# IO.net
KiCad netlist of a schematic drawn in Altium Designer
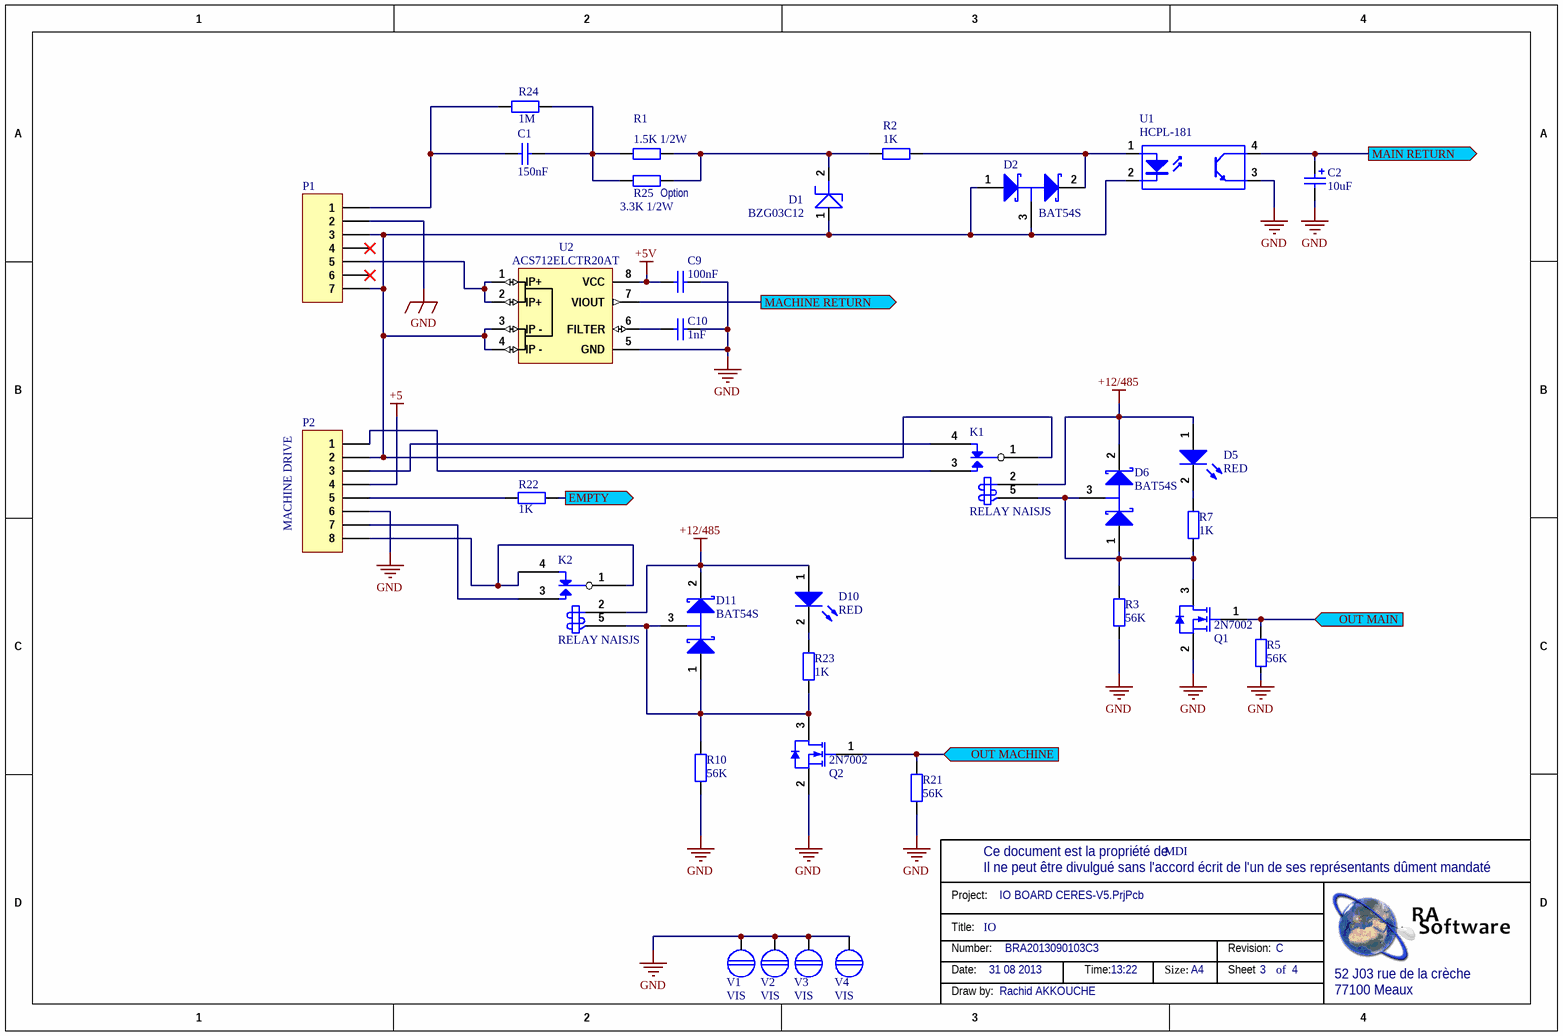
[diagram p0: IO.SchDoc]

(export (version "E")
  (design (tool "Eeschema 10.0.6"))
  (components
    (comp (ref "C1")
      (value "150nF")
      (footprint "C1210")
      (description "Capacitor")
      (fields
        (field (name "MANUFACTURER") "KEMET")
        (field (name "MANUFACTURER PART NUMBER") "C1210V154KCRACTU")
      )
      (libsource (lib "Miscellaneous Devices") (part "Cap"))
    )
    (comp (ref "C2")
      (value "10uF")
      (footprint "SYLANN:C0805")
      (description "Polarized Capacitor")
      (fields
        (field (name "MANUFACTURER") "EPCOS")
        (field (name "MANUFACTURER PART NUMBER") "B41142A4107M")
        (field (name "HAUTEUR") "7.7")
        (field (name "LONGUEUR/HAUTEUR") "7.7")
      )
      (libsource (lib "BRA") (part "Cap Pol 100uF"))
    )
    (comp (ref "C9")
      (value "100nF")
      (footprint "SYLANN:C0805")
      (description "Capacitor")
      (fields
        (field (name "MANUFACTURER") "MULTICOMP")
        (field (name "MANUFACTURER PART NUMBER") "MCCA000296")
      )
      (libsource (lib "BRA") (part "Cap 0805 100nF"))
    )
    (comp (ref "C10")
      (value "1nF")
      (footprint "SYLANN:C0805")
      (description "Capacitor")
      (fields
        (field (name "MANUFACTURER") "SAMSUNG")
        (field (name "MANUFACTURER PART NUMBER") "CL05B102KB5NNNC")
      )
      (libsource (lib "BRA") (part "Cap 0805 1nF"))
    )
    (comp (ref "D1")
      (value "BZG03C12")
      (footprint "sma")
      (fields (field (name "MANUFACTURER") "VISHAY") (field (name "MANUFACTURER PART NUMBER") "BZG03C12TR3"))
      (libsource (lib "UTIL_Library") (part "DZ"))
    )
    (comp (ref "D2")
      (value "BAT54S")
      (footprint "SOT23")
      (description "Schottky Barrier Double Diode")
      (fields (field (name "MANUFACTURER") "MULTICOMP"))
      (libsource (lib "Ares") (part "BAT54S"))
    )
    (comp (ref "D5")
      (value "HSMH-C190")
      (footprint "0603-LEDR")
      (description "Surface Mount Chip LED, Red")
      (fields
        (field (name "MANUFACTURER") "AVAGO TECHNOLOGIES")
        (field (name "MANUFACTURER PART NUMBER") "HSMH-C190.")
        (field (name "COULEUR") "RED")
        (field (name "LONGUEUR/HAUTEUR") "1.6")
      )
      (libsource (lib "BRA") (part "HSMH-C190"))
    )
    (comp (ref "D6")
      (value "BAT54S")
      (footprint "SOT23")
      (description "Schottky Barrier Double Diode")
      (fields (field (name "MANUFACTURER") "MULTICOMP"))
      (libsource (lib "Ares") (part "BAT54S"))
    )
    (comp (ref "D10")
      (value "HSMH-C190")
      (footprint "0603-LEDR")
      (description "Surface Mount Chip LED, Red")
      (fields
        (field (name "MANUFACTURER") "AVAGO TECHNOLOGIES")
        (field (name "MANUFACTURER PART NUMBER") "HSMH-C190.")
        (field (name "COULEUR") "RED")
        (field (name "LONGUEUR/HAUTEUR") "1.6")
      )
      (libsource (lib "BRA") (part "HSMH-C190"))
    )
    (comp (ref "D11")
      (value "BAT54S")
      (footprint "SOT23")
      (description "Schottky Barrier Double Diode")
      (fields (field (name "MANUFACTURER") "MULTICOMP"))
      (libsource (lib "Ares") (part "BAT54S"))
    )
    (comp (ref "K1")
      (value "RELAY NAISJS")
      (footprint "RELAIG5L")
      (fields
        (field (name "MANUFACTURER") "OMRON ELECTRONIC COMPONENTS")
        (field (name "MANUFACTURER PART NUMBER") "G5LA1A412DC")
        (field (name "HAUTEUR, DIMENSION EXTERNE") "15.8")
      )
      (libsource (lib "UTIL_Library") (part "RELAY NAISJS"))
    )
    (comp (ref "K2")
      (value "RELAY NAISJS")
      (footprint "RELAIG5L")
      (fields
        (field (name "MANUFACTURER") "OMRON ELECTRONIC COMPONENTS")
        (field (name "MANUFACTURER PART NUMBER") "G5LA1A412DC")
        (field (name "HAUTEUR, DIMENSION EXTERNE") "15.8")
      )
      (libsource (lib "UTIL_Library") (part "RELAY NAISJS"))
    )
    (comp (ref "P1")
      (value "Header 7")
      (footprint "CO7P508-90")
      (description "Header, 7-Pin")
      (fields
        (field (name "MANUFACTURER") "FCI")
        (field (name "MANUFACTURER PART NUMBER") "20020110-H071A01LF")
        (field (name "PUBLISHER") "Altium Limited")
      )
      (libsource (lib "Miscellaneous Connectors") (part "Header 7"))
    )
    (comp (ref "P2")
      (value "Header 8")
      (footprint "CO8P508 - 90°")
      (description "Header, 8-Pin")
      (fields
        (field (name "MANUFACTURER") "CAMDENBOSS")
        (field (name "MANUFACTURER PART NUMBER") "CTB9350/8AO")
        (field (name "PUBLISHER") "Altium Limited")
      )
      (libsource (lib "Miscellaneous Connectors") (part "Header 8"))
    )
    (comp (ref "Q1")
      (value "2N7002")
      (footprint "SOT23")
      (description "N-channel Enhancement Mode Field-effect Transistor")
      (fields (field (name "MANUFACTURER") "FAIRCHILD SEMICONDUCTOR"))
      (libsource (lib "BRA") (part "2N7002"))
    )
    (comp (ref "Q2")
      (value "2N7002")
      (footprint "SOT23")
      (description "N-channel Enhancement Mode Field-effect Transistor")
      (fields (field (name "MANUFACTURER") "FAIRCHILD SEMICONDUCTOR"))
      (libsource (lib "BRA") (part "2N7002"))
    )
    (comp (ref "R1")
      (value "1.5K 1/2W")
      (footprint "1206 - 2010")
      (description "Resistor")
      (fields (field (name "MANUFACTURER") "WALSIN") (field (name "MANUFACTURER PART NUMBER") "WF12P3301FTL"))
      (libsource (lib "BRA") (part "Resistor 0805 470"))
    )
    (comp (ref "R2")
      (value "1K")
      (footprint "R0805")
      (description "Resistor")
      (fields
        (field (name "MANUFACTURER") "MULTICOMP")
        (field (name "MANUFACTURER PART NUMBER") "MC0.1W08051%1KFR")
      )
      (libsource (lib "Miscellaneous Devices") (part "Res2"))
    )
    (comp (ref "R3")
      (value "56K")
      (footprint "R0805")
      (description "Resistor")
      (fields
        (field (name "MANUFACTURER") "MULTICOMP")
        (field (name "MANUFACTURER PART NUMBER") "MC0.1W08051%56KFR")
      )
      (libsource (lib "BRA") (part "Resistor 0805 56K"))
    )
    (comp (ref "R5")
      (value "56K")
      (footprint "R0805")
      (description "Resistor")
      (fields
        (field (name "MANUFACTURER") "MULTICOMP")
        (field (name "MANUFACTURER PART NUMBER") "MC0.1W08051%56KFR")
      )
      (libsource (lib "BRA") (part "Resistor 0805 56K"))
    )
    (comp (ref "R7")
      (value "1K")
      (footprint "R0805")
      (description "Resistor")
      (fields
        (field (name "MANUFACTURER") "MULTICOMP")
        (field (name "MANUFACTURER PART NUMBER") "MC0.1W08051%1KFR")
      )
      (libsource (lib "BRA") (part "Resistor 0805 1K"))
    )
    (comp (ref "R10")
      (value "56K")
      (footprint "R0805")
      (description "Resistor")
      (fields
        (field (name "MANUFACTURER") "MULTICOMP")
        (field (name "MANUFACTURER PART NUMBER") "MC0.1W08051%56KFR")
      )
      (libsource (lib "BRA") (part "Resistor 0805 56K"))
    )
    (comp (ref "R21")
      (value "56K")
      (footprint "R0805")
      (description "Resistor")
      (fields
        (field (name "MANUFACTURER") "MULTICOMP")
        (field (name "MANUFACTURER PART NUMBER") "MC0.1W08051%56KFR")
      )
      (libsource (lib "BRA") (part "Resistor 0805 56K"))
    )
    (comp (ref "R22")
      (value "1K")
      (footprint "R0805")
      (description "Resistor")
      (fields
        (field (name "MANUFACTURER") "MULTICOMP")
        (field (name "MANUFACTURER PART NUMBER") "MC0.1W08051%1KFR")
      )
      (libsource (lib "") (part "Resistor 0805 1K_1"))
    )
    (comp (ref "R23")
      (value "1K")
      (footprint "R0805")
      (description "Resistor")
      (fields
        (field (name "MANUFACTURER") "MULTICOMP")
        (field (name "MANUFACTURER PART NUMBER") "MC0.1W08051%1KFR")
      )
      (libsource (lib "BRA") (part "Resistor 0805 1K"))
    )
    (comp (ref "R24")
      (value "1M")
      (footprint "R1206")
      (description "Resistor")
      (fields
        (field (name "MANUFACTURER") "PANASONIC ELECTRONIC COMPONENTS")
        (field (name "MANUFACTURER PART NUMBER") "ERJP08F1004V")
      )
      (libsource (lib "BRA") (part "Resistor 0805 470"))
    )
    (comp (ref "R25")
      (value "3.3K 1/2W")
      (footprint "1206 - 2010")
      (description "Resistor")
      (fields (field (name "MANUFACTURER") "WALSIN") (field (name "MANUFACTURER PART NUMBER") "WF12P3301FTL"))
      (libsource (lib "BRA") (part "Resistor 0805 470"))
    )
    (comp (ref "U1")
      (value "HCPL-181")
      (footprint "OPTO-4PIN")
      (description "4-Pin Phototransistor Optocoupler")
      (fields
        (field (name "MANUFACTURER") "AVAGO TECHNOLOGIES")
        (field (name "MANUFACTURER PART NUMBER") "HCPL-181-00AE")
      )
      (libsource (lib "Miscellaneous Devices") (part "Optoisolator1"))
    )
    (comp (ref "U2")
      (value "ACS712")
      (footprint "SOIC8")
      (description "HALL EFFECT CURRENT SENSOR")
      (fields
        (field (name "MANUFACTURER") "ALLEGRO MICROSYSTEMS")
        (field (name "MANUFACTURER PART NUMBER") "ACS712ELCTR-20A-T")
        (field (name "SUPPLIER PART NUMBER 1") "ACS712ELCTR20AT")
      )
      (libsource (lib "BRA") (part "ACS712"))
    )
    (comp (ref "V1") (value "VIS") (footprint "vis42") (libsource (lib "UTIL_Library") (part "VIS")))
    (comp (ref "V2") (value "VIS") (footprint "vis42") (libsource (lib "UTIL_Library") (part "VIS")))
    (comp (ref "V3") (value "VIS") (footprint "vis42") (libsource (lib "UTIL_Library") (part "VIS")))
    (comp (ref "V4") (value "VIS") (footprint "vis42") (libsource (lib "UTIL_Library") (part "VIS")))
  )
  (nets
    (net (code "1") (name "+5") (class "Default")
      (node (ref "P2") (pin "4") (pinfunction "4_4") (pintype "passive"))
    )
    (net (code "2") (name "+5V") (class "Default")
      (node (ref "C9") (pin "2") (pinfunction "2_2") (pintype "passive"))
      (node (ref "U2") (pin "8") (pinfunction "VCC_8") (pintype "power_in"))
    )
    (net (code "3") (name "+12{slash}485") (class "Default")
      (node (ref "D10") (pin "1") (pinfunction "A_1") (pintype "passive"))
      (node (ref "D11") (pin "2") (pinfunction "K_2") (pintype "passive"))
      (node (ref "D5") (pin "1") (pinfunction "A_1") (pintype "passive"))
      (node (ref "D6") (pin "2") (pinfunction "K_2") (pintype "passive"))
      (node (ref "K1") (pin "2") (pinfunction "COIL1_2") (pintype "passive"))
      (node (ref "K2") (pin "2") (pinfunction "COIL1_2") (pintype "passive"))
    )
    (net (code "4") (name "/EMPTY") (class "Default")
      (node (ref "R22") (pin "1") (pinfunction "1_1") (pintype "passive"))
    )
    (net (code "5") (name "/MACHINE RETURN") (class "Default")
      (node (ref "U2") (pin "7") (pinfunction "VIOUT_7") (pintype "output"))
    )
    (net (code "6") (name "/MAIN RETURN") (class "Default")
      (node (ref "C2") (pin "1") (pinfunction "1_1") (pintype "passive"))
      (node (ref "U1") (pin "4") (pinfunction "C_4") (pintype "passive"))
    )
    (net (code "7") (name "/OUT MACHINE") (class "Default")
      (node (ref "Q2") (pin "1") (pinfunction "G_1") (pintype "passive"))
      (node (ref "R21") (pin "2") (pinfunction "2_2") (pintype "passive"))
    )
    (net (code "8") (name "/OUT MAIN") (class "Default")
      (node (ref "Q1") (pin "1") (pinfunction "G_1") (pintype "passive"))
      (node (ref "R5") (pin "2") (pinfunction "2_2") (pintype "passive"))
    )
    (net (code "9") (name "GND") (class "Default")
      (node (ref "C10") (pin "2") (pinfunction "2_2") (pintype "passive"))
      (node (ref "C2") (pin "2") (pinfunction "2_2") (pintype "passive"))
      (node (ref "C9") (pin "1") (pinfunction "1_1") (pintype "passive"))
      (node (ref "P1") (pin "2") (pinfunction "2_2") (pintype "passive"))
      (node (ref "P2") (pin "6") (pinfunction "6_6") (pintype "passive"))
      (node (ref "Q1") (pin "2") (pinfunction "S_2") (pintype "passive"))
      (node (ref "Q2") (pin "2") (pinfunction "S_2") (pintype "passive"))
      (node (ref "R10") (pin "1") (pinfunction "1_1") (pintype "passive"))
      (node (ref "R21") (pin "1") (pinfunction "1_1") (pintype "passive"))
      (node (ref "R3") (pin "1") (pinfunction "1_1") (pintype "passive"))
      (node (ref "R5") (pin "1") (pinfunction "1_1") (pintype "passive"))
      (node (ref "U1") (pin "3") (pinfunction "E_3") (pintype "passive"))
      (node (ref "U2") (pin "5") (pinfunction "GND_5") (pintype "power_in"))
      (node (ref "V1") (pin "1") (pinfunction "1_1") (pintype "passive"))
      (node (ref "V2") (pin "1") (pinfunction "1_1") (pintype "passive"))
      (node (ref "V3") (pin "1") (pinfunction "1_1") (pintype "passive"))
      (node (ref "V4") (pin "1") (pinfunction "1_1") (pintype "passive"))
    )
    (net (code "10") (name "Net-(C1-Pad1)") (class "Default")
      (node (ref "C1") (pin "1") (pinfunction "1_1") (pintype "passive"))
      (node (ref "P1") (pin "1") (pinfunction "1_1") (pintype "passive"))
      (node (ref "R24") (pin "2") (pinfunction "2_2") (pintype "passive"))
    )
    (net (code "11") (name "Net-(C1-Pad2)") (class "Default")
      (node (ref "C1") (pin "2") (pinfunction "2_2") (pintype "passive"))
      (node (ref "R1") (pin "2") (pinfunction "2_2") (pintype "passive"))
      (node (ref "R24") (pin "1") (pinfunction "1_1") (pintype "passive"))
      (node (ref "R25") (pin "2") (pinfunction "2_2") (pintype "passive"))
    )
    (net (code "12") (name "Net-(D1-Pad2)") (class "Default")
      (node (ref "D1") (pin "2") (pinfunction "2_2") (pintype "passive"))
      (node (ref "R1") (pin "1") (pinfunction "1_1") (pintype "passive"))
      (node (ref "R2") (pin "1") (pinfunction "1_1") (pintype "passive"))
      (node (ref "R25") (pin "1") (pinfunction "1_1") (pintype "passive"))
    )
    (net (code "13") (name "Net-(D2-A)") (class "Default")
      (node (ref "D1") (pin "1") (pinfunction "1_1") (pintype "passive"))
      (node (ref "D2") (pin "1") (pinfunction "A_1") (pintype "passive"))
      (node (ref "D2") (pin "3") (pinfunction "C_3") (pintype "passive"))
      (node (ref "K1") (pin "1") (pinfunction "COMMON_1") (pintype "passive"))
      (node (ref "P1") (pin "3") (pinfunction "3_3") (pintype "passive"))
      (node (ref "P1") (pin "7") (pinfunction "7_7") (pintype "passive"))
      (node (ref "P2") (pin "2") (pinfunction "2_2") (pintype "passive"))
      (node (ref "U1") (pin "2") (pinfunction "K_2") (pintype "passive"))
      (node (ref "U2") (pin "3") (pinfunction "IP_-_3") (pintype "bidirectional"))
      (node (ref "U2") (pin "4") (pinfunction "IP_-_4") (pintype "bidirectional"))
    )
    (net (code "14") (name "Net-(D2-K)") (class "Default")
      (node (ref "D2") (pin "2") (pinfunction "K_2") (pintype "passive"))
      (node (ref "R2") (pin "2") (pinfunction "2_2") (pintype "passive"))
      (node (ref "U1") (pin "1") (pinfunction "A_1") (pintype "passive"))
    )
    (net (code "15") (name "Net-(D5-K)") (class "Default")
      (node (ref "D5") (pin "2") (pinfunction "K_2") (pintype "passive"))
      (node (ref "R7") (pin "2") (pinfunction "2_2") (pintype "passive"))
    )
    (net (code "16") (name "Net-(D6-A)") (class "Default")
      (node (ref "D6") (pin "1") (pinfunction "A_1") (pintype "passive"))
      (node (ref "D6") (pin "3") (pinfunction "C_3") (pintype "passive"))
      (node (ref "K1") (pin "5") (pinfunction "COIL2_5") (pintype "passive"))
      (node (ref "Q1") (pin "3") (pinfunction "D_3") (pintype "passive"))
      (node (ref "R3") (pin "2") (pinfunction "2_2") (pintype "passive"))
      (node (ref "R7") (pin "1") (pinfunction "1_1") (pintype "passive"))
    )
    (net (code "17") (name "Net-(D10-K)") (class "Default")
      (node (ref "D10") (pin "2") (pinfunction "K_2") (pintype "passive"))
      (node (ref "R23") (pin "2") (pinfunction "2_2") (pintype "passive"))
    )
    (net (code "18") (name "Net-(D11-A)") (class "Default")
      (node (ref "D11") (pin "1") (pinfunction "A_1") (pintype "passive"))
      (node (ref "D11") (pin "3") (pinfunction "C_3") (pintype "passive"))
      (node (ref "K2") (pin "5") (pinfunction "COIL2_5") (pintype "passive"))
      (node (ref "Q2") (pin "3") (pinfunction "D_3") (pintype "passive"))
      (node (ref "R10") (pin "2") (pinfunction "2_2") (pintype "passive"))
      (node (ref "R23") (pin "1") (pinfunction "1_1") (pintype "passive"))
    )
    (net (code "19") (name "Net-(K1-NC)") (class "Default")
      (node (ref "K1") (pin "4") (pinfunction "NC_4") (pintype "passive"))
      (node (ref "P2") (pin "3") (pinfunction "3_3") (pintype "passive"))
    )
    (net (code "20") (name "Net-(K1-NO)") (class "Default")
      (node (ref "K1") (pin "3") (pinfunction "NO_3") (pintype "passive"))
      (node (ref "P2") (pin "1") (pinfunction "1_1") (pintype "passive"))
    )
    (net (code "21") (name "Net-(K2-COMMON)") (class "Default")
      (node (ref "K2") (pin "1") (pinfunction "COMMON_1") (pintype "passive"))
      (node (ref "K2") (pin "4") (pinfunction "NC_4") (pintype "passive"))
      (node (ref "P2") (pin "8") (pinfunction "8_8") (pintype "passive"))
    )
    (net (code "22") (name "Net-(K2-NO)") (class "Default")
      (node (ref "K2") (pin "3") (pinfunction "NO_3") (pintype "passive"))
      (node (ref "P2") (pin "7") (pinfunction "7_7") (pintype "passive"))
    )
    (net (code "23") (name "Net-(P1-Pad5)") (class "Default")
      (node (ref "P1") (pin "5") (pinfunction "5_5") (pintype "passive"))
      (node (ref "U2") (pin "1") (pinfunction "IP+_1") (pintype "bidirectional"))
      (node (ref "U2") (pin "2") (pinfunction "IP+_2") (pintype "bidirectional"))
    )
    (net (code "24") (name "Net-(P2-Pad5)") (class "Default")
      (node (ref "P2") (pin "5") (pinfunction "5_5") (pintype "passive"))
      (node (ref "R22") (pin "2") (pinfunction "2_2") (pintype "passive"))
    )
    (net (code "25") (name "Net-(U2-FILTER)") (class "Default")
      (node (ref "C10") (pin "1") (pinfunction "1_1") (pintype "passive"))
      (node (ref "U2") (pin "6") (pinfunction "FILTER_6") (pintype "bidirectional"))
    )
    (net (code "26") (name "unconnected-(P1-Pad4)") (class "Default")
      (node (ref "P1") (pin "4") (pinfunction "4_4") (pintype "passive+no_connect"))
    )
    (net (code "27") (name "unconnected-(P1-Pad6)") (class "Default")
      (node (ref "P1") (pin "6") (pinfunction "6_6") (pintype "passive+no_connect"))
    )
  )
)
